# bbb_blk.net
KiCad netlist of a schematic drawn in Altium Designer
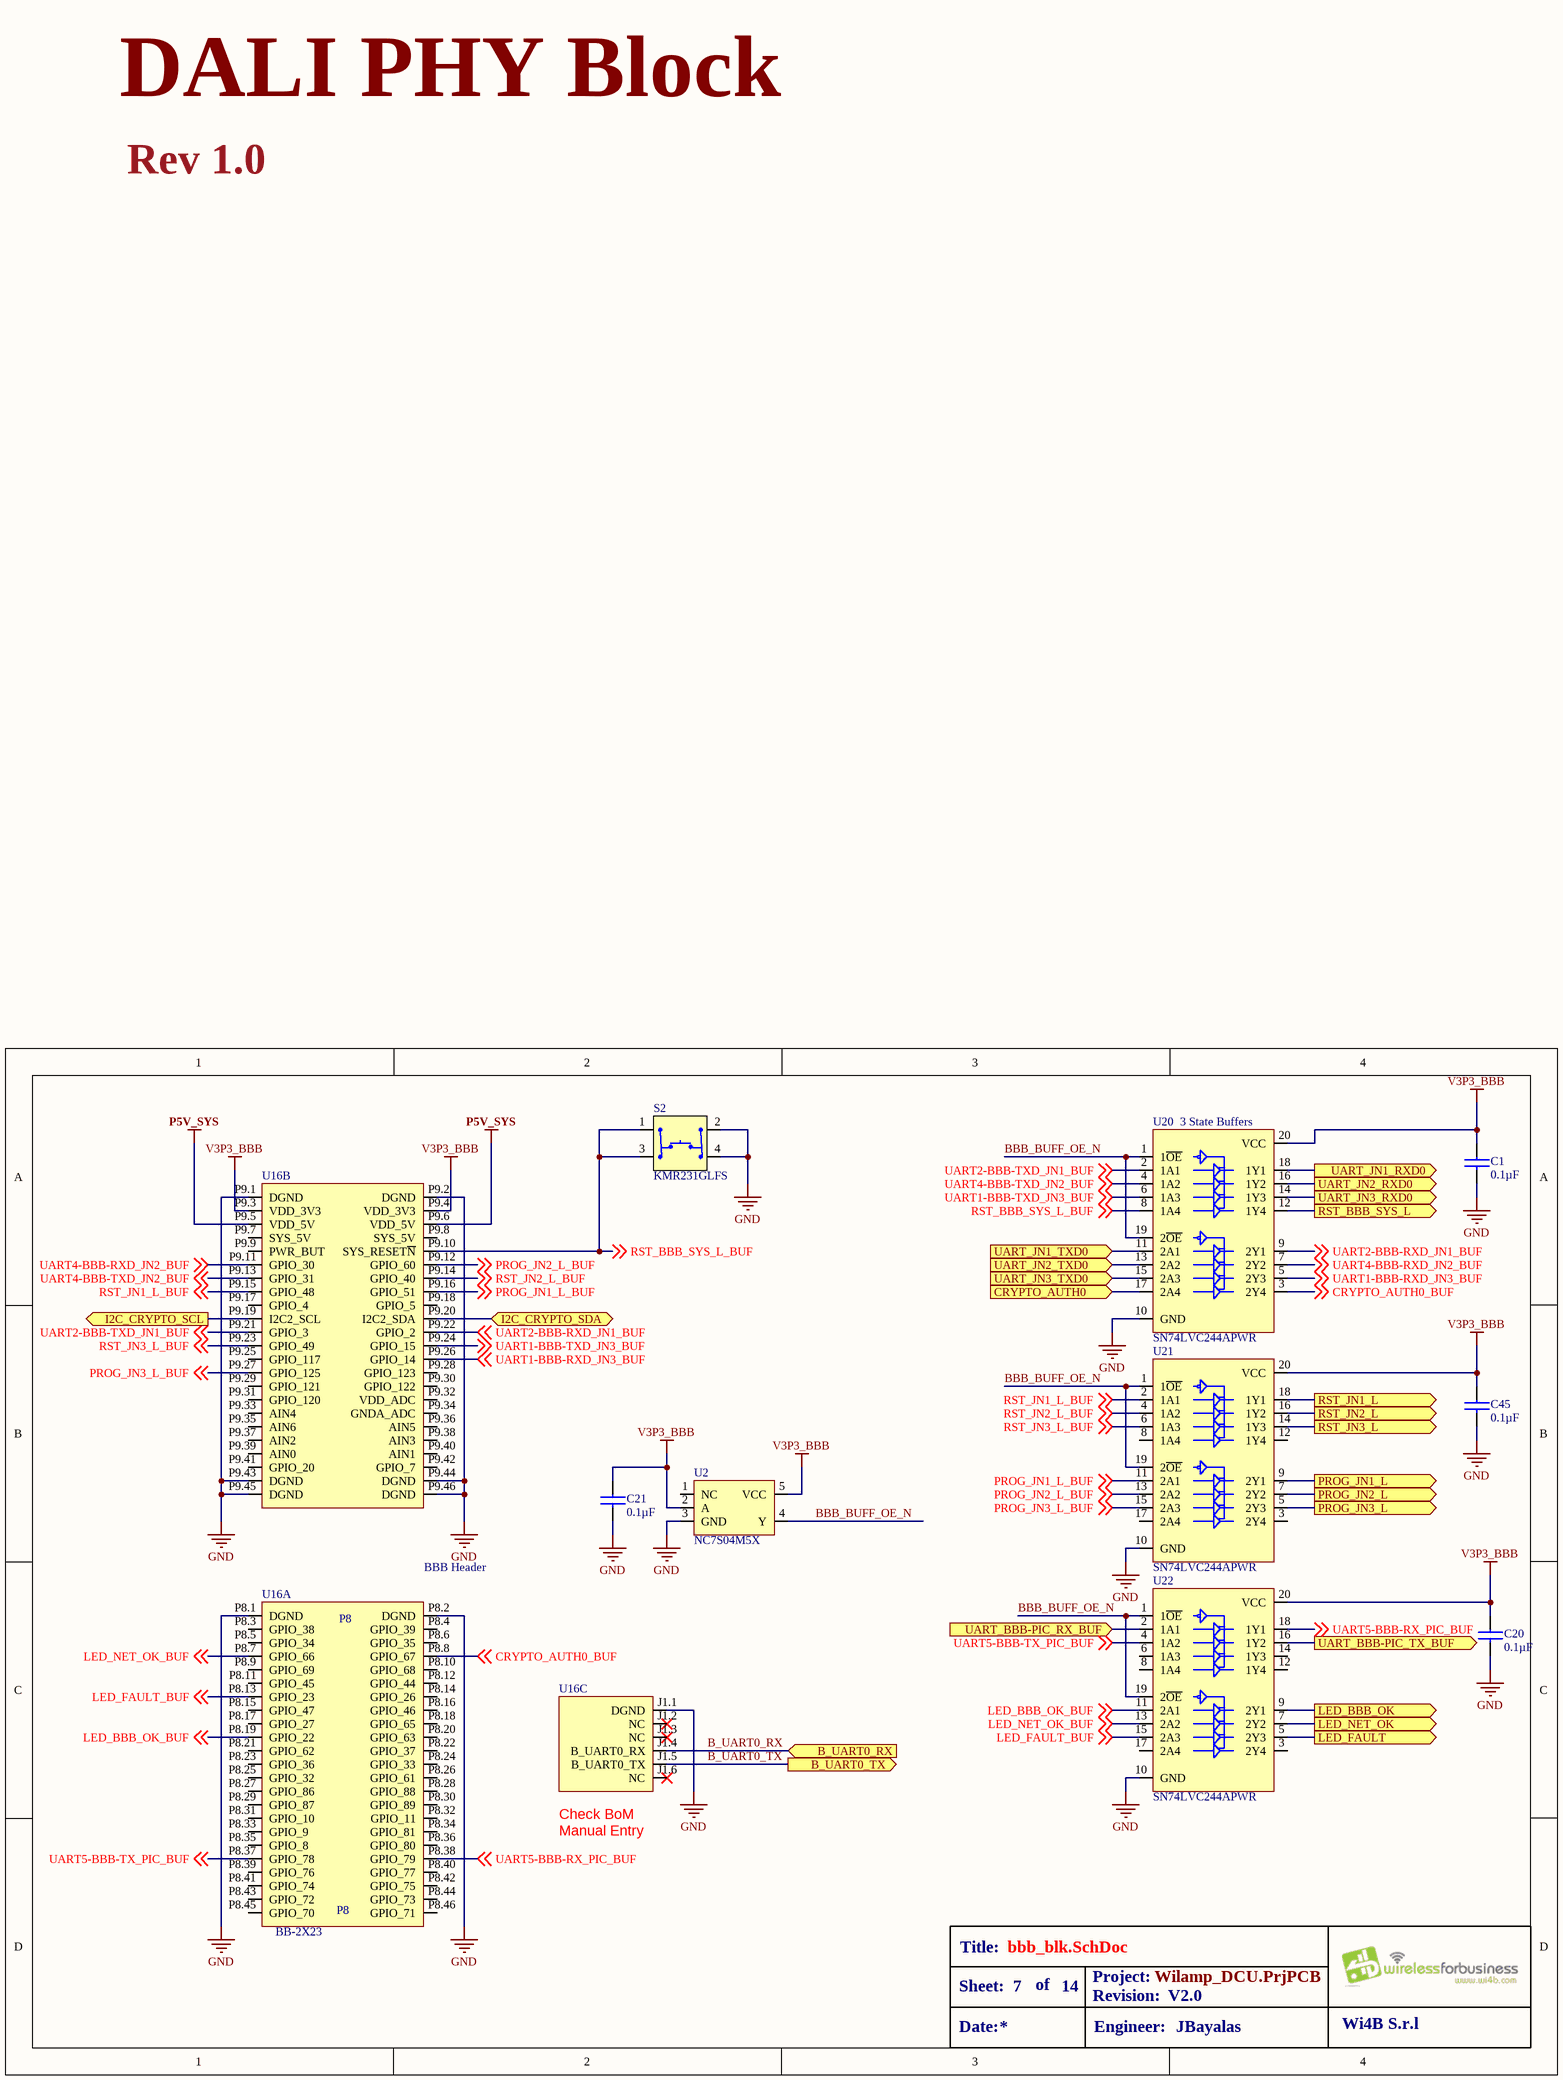
[diagram p0: bbb_blk.SchDoc]

(export (version "E")
  (design (tool "Eeschema 10.0.6"))
  (components
    (comp (ref "C1")
      (value "0.1µF")
      (footprint "C0402")
      (description "CAP CER 0.1UF 16V X7R 0402")
      (fields (field (name "MPN") "CL05B104KO3LNNC"))
      (libsource (lib "Capacitor") (part "CL05B104KO3LNNC"))
    )
    (comp (ref "C20")
      (value "0.1µF")
      (footprint "C0402")
      (description "CAP CER 0.1UF 16V X7R 0402")
      (fields (field (name "MPN") "CL05B104KO3LNNC"))
      (libsource (lib "Capacitor") (part "CL05B104KO3LNNC"))
    )
    (comp (ref "C21")
      (value "0.1µF")
      (footprint "C0402")
      (description "CAP CER 0.1UF 16V X7R 0402")
      (fields (field (name "MPN") "CL05B104KO3LNNC"))
      (libsource (lib "Capacitor") (part "CL05B104KO3LNNC"))
    )
    (comp (ref "C45")
      (value "0.1µF")
      (footprint "C0402")
      (description "CAP CER 0.1UF 16V X7R 0402")
      (fields (field (name "MPN") "CL05B104KO3LNNC"))
      (libsource (lib "Capacitor") (part "CL05B104KO3LNNC"))
    )
    (comp (ref "S2")
      (value "*")
      (footprint "KMR231G ULC LFS")
      (description "SWITCH TACTILE SPST-NO 0.05A 32V")
      (fields (field (name "MPN") "KMR231GLFS"))
      (libsource (lib "Switch") (part "KMR231GLFS"))
    )
    (comp (ref "U2")
      (value "*")
      (footprint "SOT 23-5")
      (description "IC INVERTER HS SINGLE SOT-23-5")
      (fields (field (name "MPN") "NC7S04M5X"))
      (libsource (lib "IC") (part "NC7S04M5X"))
    )
    (comp (ref "U16")
      (value "BEAGLE_BONE_BLACK_CAPE")
      (footprint "BEAGLE_BONE_BLACK_CAPE")
      (description "Beaglebone 2x23 Pin stacking header(2 Pack )")
      (fields (field (name "MPN") "BB-2X23"))
      (libsource (lib "Module") (part "BEAGLE_BONE_BLACK_CAPE"))
    )
    (comp (ref "U20")
      (value "SN74LVC244APWR")
      (footprint "TSSOP-20 (SN74LVC)")
      (description "IC BUFF/DVR TRI-ST DUAL 20TSSOP")
      (libsource (lib "IC") (part "SN74LVC244APWR"))
    )
    (comp (ref "U21")
      (value "SN74LVC244APWR")
      (footprint "TSSOP-20 (SN74LVC)")
      (description "IC BUFF/DVR TRI-ST DUAL 20TSSOP")
      (libsource (lib "IC") (part "SN74LVC244APWR"))
    )
    (comp (ref "U22")
      (value "SN74LVC244APWR")
      (footprint "TSSOP-20 (SN74LVC)")
      (description "IC BUFF/DVR TRI-ST DUAL 20TSSOP")
      (libsource (lib "IC") (part "SN74LVC244APWR"))
    )
  )
  (nets
    (net (code "1") (name "/BBB_BUFF_OE_N") (class "Default")
      (node (ref "U2") (pin "4") (pinfunction "Y_4") (pintype "passive"))
      (node (ref "U20") (pin "1") (pinfunction "1~{OE}_1") (pintype "passive"))
      (node (ref "U20") (pin "19") (pinfunction "2~{OE}_19") (pintype "passive"))
      (node (ref "U21") (pin "1") (pinfunction "1~{OE}_1") (pintype "passive"))
      (node (ref "U21") (pin "19") (pinfunction "2~{OE}_19") (pintype "passive"))
      (node (ref "U22") (pin "1") (pinfunction "1~{OE}_1") (pintype "passive"))
      (node (ref "U22") (pin "19") (pinfunction "2~{OE}_19") (pintype "passive"))
    )
    (net (code "2") (name "/B_UART0_RX") (class "Default")
      (node (ref "U16") (pin "J1.4") (pinfunction "B_UART0_RX_J1.4") (pintype "passive"))
    )
    (net (code "3") (name "/B_UART0_TX") (class "Default")
      (node (ref "U16") (pin "J1.5") (pinfunction "B_UART0_TX_J1.5") (pintype "passive"))
    )
    (net (code "4") (name "/CRYPTO_AUTH0") (class "Default")
      (node (ref "U20") (pin "17") (pinfunction "2A4_17") (pintype "passive"))
    )
    (net (code "5") (name "/I2C_CRYPTO_SCL") (class "Default")
      (node (ref "U16") (pin "P9.19") (pinfunction "I2C2_SCL_P9.19") (pintype "passive"))
    )
    (net (code "6") (name "/I2C_CRYPTO_SDA") (class "Default")
      (node (ref "U16") (pin "P9.20") (pinfunction "I2C2_SDA_P9.20") (pintype "passive"))
    )
    (net (code "7") (name "/LED_BBB_OK") (class "Default")
      (node (ref "U22") (pin "9") (pinfunction "2Y1_9") (pintype "passive"))
    )
    (net (code "8") (name "/LED_FAULT") (class "Default")
      (node (ref "U22") (pin "5") (pinfunction "2Y3_5") (pintype "passive"))
    )
    (net (code "9") (name "/LED_NET_OK") (class "Default")
      (node (ref "U22") (pin "7") (pinfunction "2Y2_7") (pintype "passive"))
    )
    (net (code "10") (name "/PROG_JN1_L") (class "Default")
      (node (ref "U21") (pin "9") (pinfunction "2Y1_9") (pintype "passive"))
    )
    (net (code "11") (name "/PROG_JN2_L") (class "Default")
      (node (ref "U21") (pin "7") (pinfunction "2Y2_7") (pintype "passive"))
    )
    (net (code "12") (name "/PROG_JN3_L") (class "Default")
      (node (ref "U21") (pin "5") (pinfunction "2Y3_5") (pintype "passive"))
    )
    (net (code "13") (name "/RST_BBB_SYS_L") (class "Default")
      (node (ref "U20") (pin "12") (pinfunction "1Y4_12") (pintype "passive"))
    )
    (net (code "14") (name "/RST_JN1_L") (class "Default")
      (node (ref "U21") (pin "18") (pinfunction "1Y1_18") (pintype "passive"))
    )
    (net (code "15") (name "/RST_JN2_L") (class "Default")
      (node (ref "U21") (pin "16") (pinfunction "1Y2_16") (pintype "passive"))
    )
    (net (code "16") (name "/RST_JN3_L") (class "Default")
      (node (ref "U21") (pin "14") (pinfunction "1Y3_14") (pintype "passive"))
    )
    (net (code "17") (name "/UART_BBB-PIC_RX_BUF") (class "Default")
      (node (ref "U22") (pin "2") (pinfunction "1A1_2") (pintype "passive"))
    )
    (net (code "18") (name "/UART_BBB-PIC_TX_BUF") (class "Default")
      (node (ref "U22") (pin "16") (pinfunction "1Y2_16") (pintype "passive"))
    )
    (net (code "19") (name "/UART_JN1_RXD0") (class "Default")
      (node (ref "U20") (pin "18") (pinfunction "1Y1_18") (pintype "passive"))
    )
    (net (code "20") (name "/UART_JN1_TXD0") (class "Default")
      (node (ref "U20") (pin "11") (pinfunction "2A1_11") (pintype "passive"))
    )
    (net (code "21") (name "/UART_JN2_RXD0") (class "Default")
      (node (ref "U20") (pin "16") (pinfunction "1Y2_16") (pintype "passive"))
    )
    (net (code "22") (name "/UART_JN2_TXD0") (class "Default")
      (node (ref "U20") (pin "13") (pinfunction "2A2_13") (pintype "passive"))
    )
    (net (code "23") (name "/UART_JN3_RXD0") (class "Default")
      (node (ref "U20") (pin "14") (pinfunction "1Y3_14") (pintype "passive"))
    )
    (net (code "24") (name "/UART_JN3_TXD0") (class "Default")
      (node (ref "U20") (pin "15") (pinfunction "2A3_15") (pintype "passive"))
    )
    (net (code "25") (name "CRYPTO_AUTH0_BUF") (class "Default")
      (node (ref "U16") (pin "P8.8") (pinfunction "GPIO_67_P8.8") (pintype "passive"))
      (node (ref "U20") (pin "3") (pinfunction "2Y4_3") (pintype "passive"))
    )
    (net (code "26") (name "GND") (class "Default")
      (node (ref "C1") (pin "2") (pinfunction "2_2") (pintype "passive"))
      (node (ref "C20") (pin "2") (pinfunction "2_2") (pintype "passive"))
      (node (ref "C21") (pin "2") (pinfunction "2_2") (pintype "passive"))
      (node (ref "C45") (pin "2") (pinfunction "2_2") (pintype "passive"))
      (node (ref "S2") (pin "2") (pinfunction "2_2") (pintype "passive"))
      (node (ref "S2") (pin "4") (pinfunction "4_4") (pintype "passive"))
      (node (ref "U16") (pin "J1.1") (pinfunction "DGND_J1.1") (pintype "passive"))
      (node (ref "U16") (pin "P8.1") (pinfunction "DGND_P8.1") (pintype "passive"))
      (node (ref "U16") (pin "P8.2") (pinfunction "DGND_P8.2") (pintype "passive"))
      (node (ref "U16") (pin "P9.1") (pinfunction "DGND_P9.1") (pintype "passive"))
      (node (ref "U16") (pin "P9.2") (pinfunction "DGND_P9.2") (pintype "passive"))
      (node (ref "U16") (pin "P9.43") (pinfunction "DGND_P9.43") (pintype "passive"))
      (node (ref "U16") (pin "P9.44") (pinfunction "DGND_P9.44") (pintype "passive"))
      (node (ref "U16") (pin "P9.45") (pinfunction "DGND_P9.45") (pintype "passive"))
      (node (ref "U16") (pin "P9.46") (pinfunction "DGND_P9.46") (pintype "passive"))
      (node (ref "U2") (pin "3") (pinfunction "GND_3") (pintype "passive"))
      (node (ref "U20") (pin "10") (pinfunction "GND_10") (pintype "passive"))
      (node (ref "U21") (pin "10") (pinfunction "GND_10") (pintype "passive"))
      (node (ref "U22") (pin "10") (pinfunction "GND_10") (pintype "passive"))
    )
    (net (code "27") (name "LED_BBB_OK_BUF") (class "Default")
      (node (ref "U16") (pin "P8.19") (pinfunction "GPIO_22_P8.19") (pintype "passive"))
      (node (ref "U22") (pin "11") (pinfunction "2A1_11") (pintype "passive"))
    )
    (net (code "28") (name "LED_FAULT_BUF") (class "Default")
      (node (ref "U16") (pin "P8.13") (pinfunction "GPIO_23_P8.13") (pintype "passive"))
      (node (ref "U22") (pin "15") (pinfunction "2A3_15") (pintype "passive"))
    )
    (net (code "29") (name "LED_NET_OK_BUF") (class "Default")
      (node (ref "U16") (pin "P8.7") (pinfunction "GPIO_66_P8.7") (pintype "passive"))
      (node (ref "U22") (pin "13") (pinfunction "2A2_13") (pintype "passive"))
    )
    (net (code "30") (name "P5V_SYS") (class "Default")
      (node (ref "U16") (pin "P9.5") (pinfunction "VDD_5V_P9.5") (pintype "passive"))
      (node (ref "U16") (pin "P9.6") (pinfunction "VDD_5V_P9.6") (pintype "passive"))
    )
    (net (code "31") (name "PROG_JN1_L_BUF") (class "Default")
      (node (ref "U16") (pin "P9.16") (pinfunction "GPIO_51_P9.16") (pintype "passive"))
      (node (ref "U21") (pin "11") (pinfunction "2A1_11") (pintype "passive"))
    )
    (net (code "32") (name "PROG_JN2_L_BUF") (class "Default")
      (node (ref "U16") (pin "P9.12") (pinfunction "GPIO_60_P9.12") (pintype "passive"))
      (node (ref "U21") (pin "13") (pinfunction "2A2_13") (pintype "passive"))
    )
    (net (code "33") (name "PROG_JN3_L_BUF") (class "Default")
      (node (ref "U16") (pin "P9.27") (pinfunction "GPIO_125_P9.27") (pintype "passive"))
      (node (ref "U21") (pin "15") (pinfunction "2A3_15") (pintype "passive"))
    )
    (net (code "34") (name "RST_BBB_SYS_L_BUF") (class "Default")
      (node (ref "S2") (pin "1") (pinfunction "1_1") (pintype "passive"))
      (node (ref "S2") (pin "3") (pinfunction "3_3") (pintype "passive"))
      (node (ref "U16") (pin "P9.10") (pinfunction "SYS_RESET~{N}_P9.10") (pintype "passive"))
      (node (ref "U20") (pin "8") (pinfunction "1A4_8") (pintype "passive"))
    )
    (net (code "35") (name "RST_JN1_L_BUF") (class "Default")
      (node (ref "U16") (pin "P9.15") (pinfunction "GPIO_48_P9.15") (pintype "passive"))
      (node (ref "U21") (pin "2") (pinfunction "1A1_2") (pintype "passive"))
    )
    (net (code "36") (name "RST_JN2_L_BUF") (class "Default")
      (node (ref "U16") (pin "P9.14") (pinfunction "GPIO_40_P9.14") (pintype "passive"))
      (node (ref "U21") (pin "4") (pinfunction "1A2_4") (pintype "passive"))
    )
    (net (code "37") (name "RST_JN3_L_BUF") (class "Default")
      (node (ref "U16") (pin "P9.23") (pinfunction "GPIO_49_P9.23") (pintype "passive"))
      (node (ref "U21") (pin "6") (pinfunction "1A3_6") (pintype "passive"))
    )
    (net (code "38") (name "UART1-BBB-RXD_JN3_BUF") (class "Default")
      (node (ref "U16") (pin "P9.26") (pinfunction "GPIO_14_P9.26") (pintype "passive"))
      (node (ref "U20") (pin "5") (pinfunction "2Y3_5") (pintype "passive"))
    )
    (net (code "39") (name "UART1-BBB-TXD_JN3_BUF") (class "Default")
      (node (ref "U16") (pin "P9.24") (pinfunction "GPIO_15_P9.24") (pintype "passive"))
      (node (ref "U20") (pin "6") (pinfunction "1A3_6") (pintype "passive"))
    )
    (net (code "40") (name "UART2-BBB-RXD_JN1_BUF") (class "Default")
      (node (ref "U16") (pin "P9.22") (pinfunction "GPIO_2_P9.22") (pintype "passive"))
      (node (ref "U20") (pin "9") (pinfunction "2Y1_9") (pintype "passive"))
    )
    (net (code "41") (name "UART2-BBB-TXD_JN1_BUF") (class "Default")
      (node (ref "U16") (pin "P9.21") (pinfunction "GPIO_3_P9.21") (pintype "passive"))
      (node (ref "U20") (pin "2") (pinfunction "1A1_2") (pintype "passive"))
    )
    (net (code "42") (name "UART4-BBB-RXD_JN2_BUF") (class "Default")
      (node (ref "U16") (pin "P9.11") (pinfunction "GPIO_30_P9.11") (pintype "passive"))
      (node (ref "U20") (pin "7") (pinfunction "2Y2_7") (pintype "passive"))
    )
    (net (code "43") (name "UART4-BBB-TXD_JN2_BUF") (class "Default")
      (node (ref "U16") (pin "P9.13") (pinfunction "GPIO_31_P9.13") (pintype "passive"))
      (node (ref "U20") (pin "4") (pinfunction "1A2_4") (pintype "passive"))
    )
    (net (code "44") (name "UART5-BBB-RX_PIC_BUF") (class "Default")
      (node (ref "U16") (pin "P8.38") (pinfunction "GPIO_79_P8.38") (pintype "passive"))
      (node (ref "U22") (pin "18") (pinfunction "1Y1_18") (pintype "passive"))
    )
    (net (code "45") (name "UART5-BBB-TX_PIC_BUF") (class "Default")
      (node (ref "U16") (pin "P8.37") (pinfunction "GPIO_78_P8.37") (pintype "passive"))
      (node (ref "U22") (pin "4") (pinfunction "1A2_4") (pintype "passive"))
    )
    (net (code "46") (name "V3P3_BBB") (class "Default")
      (node (ref "C1") (pin "1") (pinfunction "1_1") (pintype "passive"))
      (node (ref "C20") (pin "1") (pinfunction "1_1") (pintype "passive"))
      (node (ref "C21") (pin "1") (pinfunction "1_1") (pintype "passive"))
      (node (ref "C45") (pin "1") (pinfunction "1_1") (pintype "passive"))
      (node (ref "U16") (pin "P9.3") (pinfunction "VDD_3V3_P9.3") (pintype "passive"))
      (node (ref "U16") (pin "P9.4") (pinfunction "VDD_3V3_P9.4") (pintype "passive"))
      (node (ref "U2") (pin "2") (pinfunction "A_2") (pintype "passive"))
      (node (ref "U2") (pin "5") (pinfunction "VCC_5") (pintype "passive"))
      (node (ref "U20") (pin "20") (pinfunction "VCC_20") (pintype "passive"))
      (node (ref "U21") (pin "20") (pinfunction "VCC_20") (pintype "passive"))
      (node (ref "U22") (pin "20") (pinfunction "VCC_20") (pintype "passive"))
    )
    (net (code "47") (name "unconnected-(U2-NC-Pad1)") (class "Default")
      (node (ref "U2") (pin "1") (pinfunction "NC_1") (pintype "passive"))
    )
    (net (code "48") (name "unconnected-(U16A-GPIO_8-PadP8.35)") (class "Default")
      (node (ref "U16") (pin "P8.35") (pinfunction "GPIO_8_P8.35") (pintype "passive"))
    )
    (net (code "49") (name "unconnected-(U16A-GPIO_9-PadP8.33)") (class "Default")
      (node (ref "U16") (pin "P8.33") (pinfunction "GPIO_9_P8.33") (pintype "passive"))
    )
    (net (code "50") (name "unconnected-(U16A-GPIO_10-PadP8.31)") (class "Default")
      (node (ref "U16") (pin "P8.31") (pinfunction "GPIO_10_P8.31") (pintype "passive"))
    )
    (net (code "51") (name "unconnected-(U16A-GPIO_11-PadP8.32)") (class "Default")
      (node (ref "U16") (pin "P8.32") (pinfunction "GPIO_11_P8.32") (pintype "passive"))
    )
    (net (code "52") (name "unconnected-(U16A-GPIO_26-PadP8.14)") (class "Default")
      (node (ref "U16") (pin "P8.14") (pinfunction "GPIO_26_P8.14") (pintype "passive"))
    )
    (net (code "53") (name "unconnected-(U16A-GPIO_27-PadP8.17)") (class "Default")
      (node (ref "U16") (pin "P8.17") (pinfunction "GPIO_27_P8.17") (pintype "passive"))
    )
    (net (code "54") (name "unconnected-(U16A-GPIO_32-PadP8.25)") (class "Default")
      (node (ref "U16") (pin "P8.25") (pinfunction "GPIO_32_P8.25") (pintype "passive"))
    )
    (net (code "55") (name "unconnected-(U16A-GPIO_33-PadP8.24)") (class "Default")
      (node (ref "U16") (pin "P8.24") (pinfunction "GPIO_33_P8.24") (pintype "passive"))
    )
    (net (code "56") (name "unconnected-(U16A-GPIO_34-PadP8.5)") (class "Default")
      (node (ref "U16") (pin "P8.5") (pinfunction "GPIO_34_P8.5") (pintype "passive"))
    )
    (net (code "57") (name "unconnected-(U16A-GPIO_35-PadP8.6)") (class "Default")
      (node (ref "U16") (pin "P8.6") (pinfunction "GPIO_35_P8.6") (pintype "passive"))
    )
    (net (code "58") (name "unconnected-(U16A-GPIO_36-PadP8.23)") (class "Default")
      (node (ref "U16") (pin "P8.23") (pinfunction "GPIO_36_P8.23") (pintype "passive"))
    )
    (net (code "59") (name "unconnected-(U16A-GPIO_37-PadP8.22)") (class "Default")
      (node (ref "U16") (pin "P8.22") (pinfunction "GPIO_37_P8.22") (pintype "passive"))
    )
    (net (code "60") (name "unconnected-(U16A-GPIO_38-PadP8.3)") (class "Default")
      (node (ref "U16") (pin "P8.3") (pinfunction "GPIO_38_P8.3") (pintype "passive"))
    )
    (net (code "61") (name "unconnected-(U16A-GPIO_39-PadP8.4)") (class "Default")
      (node (ref "U16") (pin "P8.4") (pinfunction "GPIO_39_P8.4") (pintype "passive"))
    )
    (net (code "62") (name "unconnected-(U16A-GPIO_44-PadP8.12)") (class "Default")
      (node (ref "U16") (pin "P8.12") (pinfunction "GPIO_44_P8.12") (pintype "passive"))
    )
    (net (code "63") (name "unconnected-(U16A-GPIO_45-PadP8.11)") (class "Default")
      (node (ref "U16") (pin "P8.11") (pinfunction "GPIO_45_P8.11") (pintype "passive"))
    )
    (net (code "64") (name "unconnected-(U16A-GPIO_46-PadP8.16)") (class "Default")
      (node (ref "U16") (pin "P8.16") (pinfunction "GPIO_46_P8.16") (pintype "passive"))
    )
    (net (code "65") (name "unconnected-(U16A-GPIO_47-PadP8.15)") (class "Default")
      (node (ref "U16") (pin "P8.15") (pinfunction "GPIO_47_P8.15") (pintype "passive"))
    )
    (net (code "66") (name "unconnected-(U16A-GPIO_61-PadP8.26)") (class "Default")
      (node (ref "U16") (pin "P8.26") (pinfunction "GPIO_61_P8.26") (pintype "passive"))
    )
    (net (code "67") (name "unconnected-(U16A-GPIO_62-PadP8.21)") (class "Default")
      (node (ref "U16") (pin "P8.21") (pinfunction "GPIO_62_P8.21") (pintype "passive"))
    )
    (net (code "68") (name "unconnected-(U16A-GPIO_63-PadP8.20)") (class "Default")
      (node (ref "U16") (pin "P8.20") (pinfunction "GPIO_63_P8.20") (pintype "passive"))
    )
    (net (code "69") (name "unconnected-(U16A-GPIO_65-PadP8.18)") (class "Default")
      (node (ref "U16") (pin "P8.18") (pinfunction "GPIO_65_P8.18") (pintype "passive"))
    )
    (net (code "70") (name "unconnected-(U16A-GPIO_68-PadP8.10)") (class "Default")
      (node (ref "U16") (pin "P8.10") (pinfunction "GPIO_68_P8.10") (pintype "passive"))
    )
    (net (code "71") (name "unconnected-(U16A-GPIO_69-PadP8.9)") (class "Default")
      (node (ref "U16") (pin "P8.9") (pinfunction "GPIO_69_P8.9") (pintype "passive"))
    )
    (net (code "72") (name "unconnected-(U16A-GPIO_70-PadP8.45)") (class "Default")
      (node (ref "U16") (pin "P8.45") (pinfunction "GPIO_70_P8.45") (pintype "passive"))
    )
    (net (code "73") (name "unconnected-(U16A-GPIO_71-PadP8.46)") (class "Default")
      (node (ref "U16") (pin "P8.46") (pinfunction "GPIO_71_P8.46") (pintype "passive"))
    )
    (net (code "74") (name "unconnected-(U16A-GPIO_72-PadP8.43)") (class "Default")
      (node (ref "U16") (pin "P8.43") (pinfunction "GPIO_72_P8.43") (pintype "passive"))
    )
    (net (code "75") (name "unconnected-(U16A-GPIO_73-PadP8.44)") (class "Default")
      (node (ref "U16") (pin "P8.44") (pinfunction "GPIO_73_P8.44") (pintype "passive"))
    )
    (net (code "76") (name "unconnected-(U16A-GPIO_74-PadP8.41)") (class "Default")
      (node (ref "U16") (pin "P8.41") (pinfunction "GPIO_74_P8.41") (pintype "passive"))
    )
    (net (code "77") (name "unconnected-(U16A-GPIO_75-PadP8.42)") (class "Default")
      (node (ref "U16") (pin "P8.42") (pinfunction "GPIO_75_P8.42") (pintype "passive"))
    )
    (net (code "78") (name "unconnected-(U16A-GPIO_76-PadP8.39)") (class "Default")
      (node (ref "U16") (pin "P8.39") (pinfunction "GPIO_76_P8.39") (pintype "passive"))
    )
    (net (code "79") (name "unconnected-(U16A-GPIO_77-PadP8.40)") (class "Default")
      (node (ref "U16") (pin "P8.40") (pinfunction "GPIO_77_P8.40") (pintype "passive"))
    )
    (net (code "80") (name "unconnected-(U16A-GPIO_80-PadP8.36)") (class "Default")
      (node (ref "U16") (pin "P8.36") (pinfunction "GPIO_80_P8.36") (pintype "passive"))
    )
    (net (code "81") (name "unconnected-(U16A-GPIO_81-PadP8.34)") (class "Default")
      (node (ref "U16") (pin "P8.34") (pinfunction "GPIO_81_P8.34") (pintype "passive"))
    )
    (net (code "82") (name "unconnected-(U16A-GPIO_86-PadP8.27)") (class "Default")
      (node (ref "U16") (pin "P8.27") (pinfunction "GPIO_86_P8.27") (pintype "passive"))
    )
    (net (code "83") (name "unconnected-(U16A-GPIO_87-PadP8.29)") (class "Default")
      (node (ref "U16") (pin "P8.29") (pinfunction "GPIO_87_P8.29") (pintype "passive"))
    )
    (net (code "84") (name "unconnected-(U16A-GPIO_88-PadP8.28)") (class "Default")
      (node (ref "U16") (pin "P8.28") (pinfunction "GPIO_88_P8.28") (pintype "passive"))
    )
    (net (code "85") (name "unconnected-(U16A-GPIO_89-PadP8.30)") (class "Default")
      (node (ref "U16") (pin "P8.30") (pinfunction "GPIO_89_P8.30") (pintype "passive"))
    )
    (net (code "86") (name "unconnected-(U16B-AIN0-PadP9.39)") (class "Default")
      (node (ref "U16") (pin "P9.39") (pinfunction "AIN0_P9.39") (pintype "passive"))
    )
    (net (code "87") (name "unconnected-(U16B-AIN1-PadP9.40)") (class "Default")
      (node (ref "U16") (pin "P9.40") (pinfunction "AIN1_P9.40") (pintype "passive"))
    )
    (net (code "88") (name "unconnected-(U16B-AIN2-PadP9.37)") (class "Default")
      (node (ref "U16") (pin "P9.37") (pinfunction "AIN2_P9.37") (pintype "passive"))
    )
    (net (code "89") (name "unconnected-(U16B-AIN3-PadP9.38)") (class "Default")
      (node (ref "U16") (pin "P9.38") (pinfunction "AIN3_P9.38") (pintype "passive"))
    )
    (net (code "90") (name "unconnected-(U16B-AIN4-PadP9.33)") (class "Default")
      (node (ref "U16") (pin "P9.33") (pinfunction "AIN4_P9.33") (pintype "passive"))
    )
    (net (code "91") (name "unconnected-(U16B-AIN5-PadP9.36)") (class "Default")
      (node (ref "U16") (pin "P9.36") (pinfunction "AIN5_P9.36") (pintype "passive"))
    )
    (net (code "92") (name "unconnected-(U16B-AIN6-PadP9.35)") (class "Default")
      (node (ref "U16") (pin "P9.35") (pinfunction "AIN6_P9.35") (pintype "passive"))
    )
    (net (code "93") (name "unconnected-(U16B-GNDA_ADC-PadP9.34)") (class "Default")
      (node (ref "U16") (pin "P9.34") (pinfunction "GNDA_ADC_P9.34") (pintype "passive"))
    )
    (net (code "94") (name "unconnected-(U16B-GPIO_4-PadP9.17)") (class "Default")
      (node (ref "U16") (pin "P9.17") (pinfunction "GPIO_4_P9.17") (pintype "passive"))
    )
    (net (code "95") (name "unconnected-(U16B-GPIO_5-PadP9.18)") (class "Default")
      (node (ref "U16") (pin "P9.18") (pinfunction "GPIO_5_P9.18") (pintype "passive"))
    )
    (net (code "96") (name "unconnected-(U16B-GPIO_7-PadP9.42)") (class "Default")
      (node (ref "U16") (pin "P9.42") (pinfunction "GPIO_7_P9.42") (pintype "passive"))
    )
    (net (code "97") (name "unconnected-(U16B-GPIO_20-PadP9.41)") (class "Default")
      (node (ref "U16") (pin "P9.41") (pinfunction "GPIO_20_P9.41") (pintype "passive"))
    )
    (net (code "98") (name "unconnected-(U16B-GPIO_117-PadP9.25)") (class "Default")
      (node (ref "U16") (pin "P9.25") (pinfunction "GPIO_117_P9.25") (pintype "passive"))
    )
    (net (code "99") (name "unconnected-(U16B-GPIO_120-PadP9.31)") (class "Default")
      (node (ref "U16") (pin "P9.31") (pinfunction "GPIO_120_P9.31") (pintype "passive"))
    )
    (net (code "100") (name "unconnected-(U16B-GPIO_121-PadP9.29)") (class "Default")
      (node (ref "U16") (pin "P9.29") (pinfunction "GPIO_121_P9.29") (pintype "passive"))
    )
    (net (code "101") (name "unconnected-(U16B-GPIO_122-PadP9.30)") (class "Default")
      (node (ref "U16") (pin "P9.30") (pinfunction "GPIO_122_P9.30") (pintype "passive"))
    )
    (net (code "102") (name "unconnected-(U16B-GPIO_123-PadP9.28)") (class "Default")
      (node (ref "U16") (pin "P9.28") (pinfunction "GPIO_123_P9.28") (pintype "passive"))
    )
    (net (code "103") (name "unconnected-(U16B-PWR_BUT-PadP9.9)") (class "Default")
      (node (ref "U16") (pin "P9.9") (pinfunction "PWR_BUT_P9.9") (pintype "passive"))
    )
    (net (code "104") (name "unconnected-(U16B-SYS_5V-PadP9.7)") (class "Default")
      (node (ref "U16") (pin "P9.7") (pinfunction "SYS_5V_P9.7") (pintype "passive"))
    )
    (net (code "105") (name "unconnected-(U16B-SYS_5V-PadP9.8)") (class "Default")
      (node (ref "U16") (pin "P9.8") (pinfunction "SYS_5V_P9.8") (pintype "passive"))
    )
    (net (code "106") (name "unconnected-(U16B-VDD_ADC-PadP9.32)") (class "Default")
      (node (ref "U16") (pin "P9.32") (pinfunction "VDD_ADC_P9.32") (pintype "passive"))
    )
    (net (code "107") (name "unconnected-(U16C-NC-PadJ1.2)") (class "Default")
      (node (ref "U16") (pin "J1.2") (pinfunction "NC_J1.2") (pintype "passive+no_connect"))
    )
    (net (code "108") (name "unconnected-(U16C-NC-PadJ1.3)") (class "Default")
      (node (ref "U16") (pin "J1.3") (pinfunction "NC_J1.3") (pintype "passive+no_connect"))
    )
    (net (code "109") (name "unconnected-(U16C-NC-PadJ1.6)") (class "Default")
      (node (ref "U16") (pin "J1.6") (pinfunction "NC_J1.6") (pintype "passive+no_connect"))
    )
    (net (code "110") (name "unconnected-(U21-1A4-Pad8)") (class "Default")
      (node (ref "U21") (pin "8") (pinfunction "1A4_8") (pintype "passive"))
    )
    (net (code "111") (name "unconnected-(U21-1Y4-Pad12)") (class "Default")
      (node (ref "U21") (pin "12") (pinfunction "1Y4_12") (pintype "passive"))
    )
    (net (code "112") (name "unconnected-(U21-2A4-Pad17)") (class "Default")
      (node (ref "U21") (pin "17") (pinfunction "2A4_17") (pintype "passive"))
    )
    (net (code "113") (name "unconnected-(U21-2Y4-Pad3)") (class "Default")
      (node (ref "U21") (pin "3") (pinfunction "2Y4_3") (pintype "passive"))
    )
    (net (code "114") (name "unconnected-(U22-1A3-Pad6)") (class "Default")
      (node (ref "U22") (pin "6") (pinfunction "1A3_6") (pintype "passive"))
    )
    (net (code "115") (name "unconnected-(U22-1A4-Pad8)") (class "Default")
      (node (ref "U22") (pin "8") (pinfunction "1A4_8") (pintype "passive"))
    )
    (net (code "116") (name "unconnected-(U22-1Y3-Pad14)") (class "Default")
      (node (ref "U22") (pin "14") (pinfunction "1Y3_14") (pintype "passive"))
    )
    (net (code "117") (name "unconnected-(U22-1Y4-Pad12)") (class "Default")
      (node (ref "U22") (pin "12") (pinfunction "1Y4_12") (pintype "passive"))
    )
    (net (code "118") (name "unconnected-(U22-2A4-Pad17)") (class "Default")
      (node (ref "U22") (pin "17") (pinfunction "2A4_17") (pintype "passive"))
    )
    (net (code "119") (name "unconnected-(U22-2Y4-Pad3)") (class "Default")
      (node (ref "U22") (pin "3") (pinfunction "2Y4_3") (pintype "passive"))
    )
  )
)
